# dcdc_mc34063_up_5to12.net
KiCad netlist of a schematic drawn in EAGLE
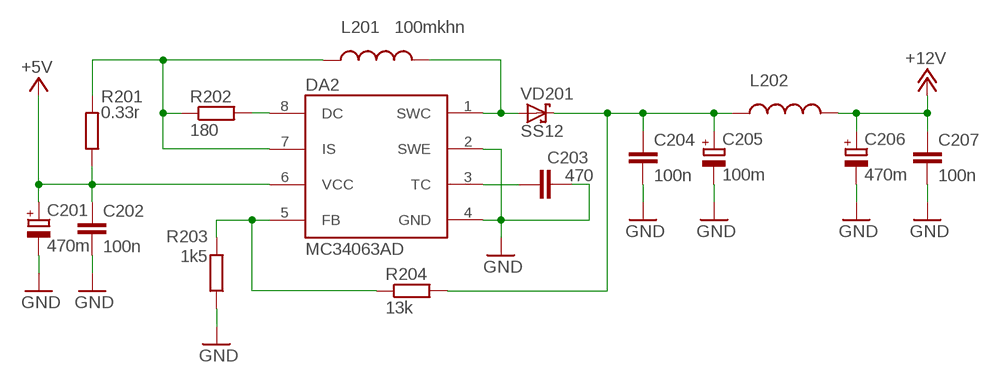
[diagram p0: schematic, sheet 1]

(export (version "E")
  (design (tool "Eeschema 10.0.6"))
  (components
    (comp (ref "C201")
      (value "470m")
      (footprint "eagle-import:E3,5-8")
      (libsource (lib "eagle-import") (part "CPOL-EUE3.5-8"))
    )
    (comp (ref "C202")
      (value "100n")
      (footprint "eagle-import:C0805")
      (libsource (lib "eagle-import") (part "C-EUC0805"))
    )
    (comp (ref "C203")
      (value "470")
      (footprint "eagle-import:C0805")
      (libsource (lib "eagle-import") (part "C-EUC0805"))
    )
    (comp (ref "C204")
      (value "100n")
      (footprint "eagle-import:C0805")
      (libsource (lib "eagle-import") (part "C-EUC0805"))
    )
    (comp (ref "C205")
      (value "100m")
      (footprint "eagle-import:E2,5-5")
      (libsource (lib "eagle-import") (part "CPOL-EUE2.5-5"))
    )
    (comp (ref "C206")
      (value "470m")
      (footprint "eagle-import:E3,5-8")
      (libsource (lib "eagle-import") (part "CPOL-EUE3.5-8"))
    )
    (comp (ref "C207")
      (value "100n")
      (footprint "eagle-import:C0805")
      (libsource (lib "eagle-import") (part "C-EUC0805"))
    )
    (comp (ref "DA2")
      (value "MC34063AD")
      (footprint "eagle-import:SOIC8")
      (libsource (lib "eagle-import") (part "MC34063AD"))
    )
    (comp (ref "L201")
      (value "100mkhn")
      (footprint "eagle-import:TFI0305")
      (libsource (lib "eagle-import") (part "L-USTFI0305"))
    )
    (comp (ref "L202")
      (value "L-US0204/7")
      (footprint "eagle-import:0204_7")
      (libsource (lib "eagle-import") (part "L-US0204/7"))
    )
    (comp (ref "R201")
      (value "0.33r")
      (footprint "eagle-import:M1206")
      (libsource (lib "eagle-import") (part "R-EU_M1206"))
    )
    (comp (ref "R202")
      (value "180")
      (footprint "eagle-import:M0805")
      (libsource (lib "eagle-import") (part "R-EU_M0805"))
    )
    (comp (ref "R203")
      (value "1k5")
      (footprint "eagle-import:M0805")
      (libsource (lib "eagle-import") (part "R-EU_M0805"))
    )
    (comp (ref "R204")
      (value "13k")
      (footprint "eagle-import:M0805")
      (libsource (lib "eagle-import") (part "R-EU_M0805"))
    )
    (comp (ref "VD201")
      (value "SS12")
      (footprint "eagle-import:SMB")
      (libsource (lib "eagle-import") (part "SCHOTTKY-DIODESMD"))
    )
  )
  (nets
    (net (code "1") (name "+5V") (class "Default")
      (node (ref "C201") (pin "+") (pinfunction "+_+") (pintype "passive"))
      (node (ref "C202") (pin "1") (pinfunction "1_1") (pintype "passive"))
      (node (ref "DA2") (pin "6") (pinfunction "VCC_6") (pintype "passive"))
      (node (ref "R201") (pin "1") (pinfunction "1_1") (pintype "passive"))
    )
    (net (code "2") (name "+12V") (class "Default")
      (node (ref "C206") (pin "+") (pinfunction "+_+") (pintype "passive"))
      (node (ref "C207") (pin "1") (pinfunction "1_1") (pintype "passive"))
      (node (ref "L202") (pin "2") (pinfunction "2_2") (pintype "passive"))
    )
    (net (code "3") (name "GND") (class "Default")
      (node (ref "C201") (pin "-") (pinfunction "-_-") (pintype "passive"))
      (node (ref "C202") (pin "2") (pinfunction "2_2") (pintype "passive"))
      (node (ref "C203") (pin "2") (pinfunction "2_2") (pintype "passive"))
      (node (ref "C204") (pin "2") (pinfunction "2_2") (pintype "passive"))
      (node (ref "C205") (pin "-") (pinfunction "-_-") (pintype "passive"))
      (node (ref "C206") (pin "-") (pinfunction "-_-") (pintype "passive"))
      (node (ref "C207") (pin "2") (pinfunction "2_2") (pintype "passive"))
      (node (ref "DA2") (pin "2") (pinfunction "SWE_2") (pintype "passive"))
      (node (ref "DA2") (pin "4") (pinfunction "GND_4") (pintype "passive"))
      (node (ref "R203") (pin "1") (pinfunction "1_1") (pintype "passive"))
    )
    (net (code "4") (name "Net-(C204-Pad1)") (class "Default")
      (node (ref "C204") (pin "1") (pinfunction "1_1") (pintype "passive"))
      (node (ref "C205") (pin "+") (pinfunction "+_+") (pintype "passive"))
      (node (ref "L202") (pin "1") (pinfunction "1_1") (pintype "passive"))
      (node (ref "R204") (pin "2") (pinfunction "2_2") (pintype "passive"))
      (node (ref "VD201") (pin "C") (pinfunction "C_C") (pintype "passive"))
    )
    (net (code "5") (name "Net-(DA2-DC)") (class "Default")
      (node (ref "DA2") (pin "8") (pinfunction "DC_8") (pintype "passive"))
      (node (ref "R202") (pin "2") (pinfunction "2_2") (pintype "passive"))
    )
    (net (code "6") (name "Net-(DA2-FB)") (class "Default")
      (node (ref "DA2") (pin "5") (pinfunction "FB_5") (pintype "passive"))
      (node (ref "R203") (pin "2") (pinfunction "2_2") (pintype "passive"))
      (node (ref "R204") (pin "1") (pinfunction "1_1") (pintype "passive"))
    )
    (net (code "7") (name "Net-(DA2-IS)") (class "Default")
      (node (ref "DA2") (pin "7") (pinfunction "IS_7") (pintype "passive"))
      (node (ref "L201") (pin "1") (pinfunction "1_1") (pintype "passive"))
      (node (ref "R201") (pin "2") (pinfunction "2_2") (pintype "passive"))
      (node (ref "R202") (pin "1") (pinfunction "1_1") (pintype "passive"))
    )
    (net (code "8") (name "Net-(DA2-SWC)") (class "Default")
      (node (ref "DA2") (pin "1") (pinfunction "SWC_1") (pintype "passive"))
      (node (ref "L201") (pin "2") (pinfunction "2_2") (pintype "passive"))
      (node (ref "VD201") (pin "A") (pinfunction "A_A") (pintype "passive"))
    )
    (net (code "9") (name "Net-(DA2-TC)") (class "Default")
      (node (ref "C203") (pin "1") (pinfunction "1_1") (pintype "passive"))
      (node (ref "DA2") (pin "3") (pinfunction "TC_3") (pintype "passive"))
    )
  )
)
